# Mainboard_Motordriver_Interface.net
KiCad netlist of a schematic drawn in Altium Designer
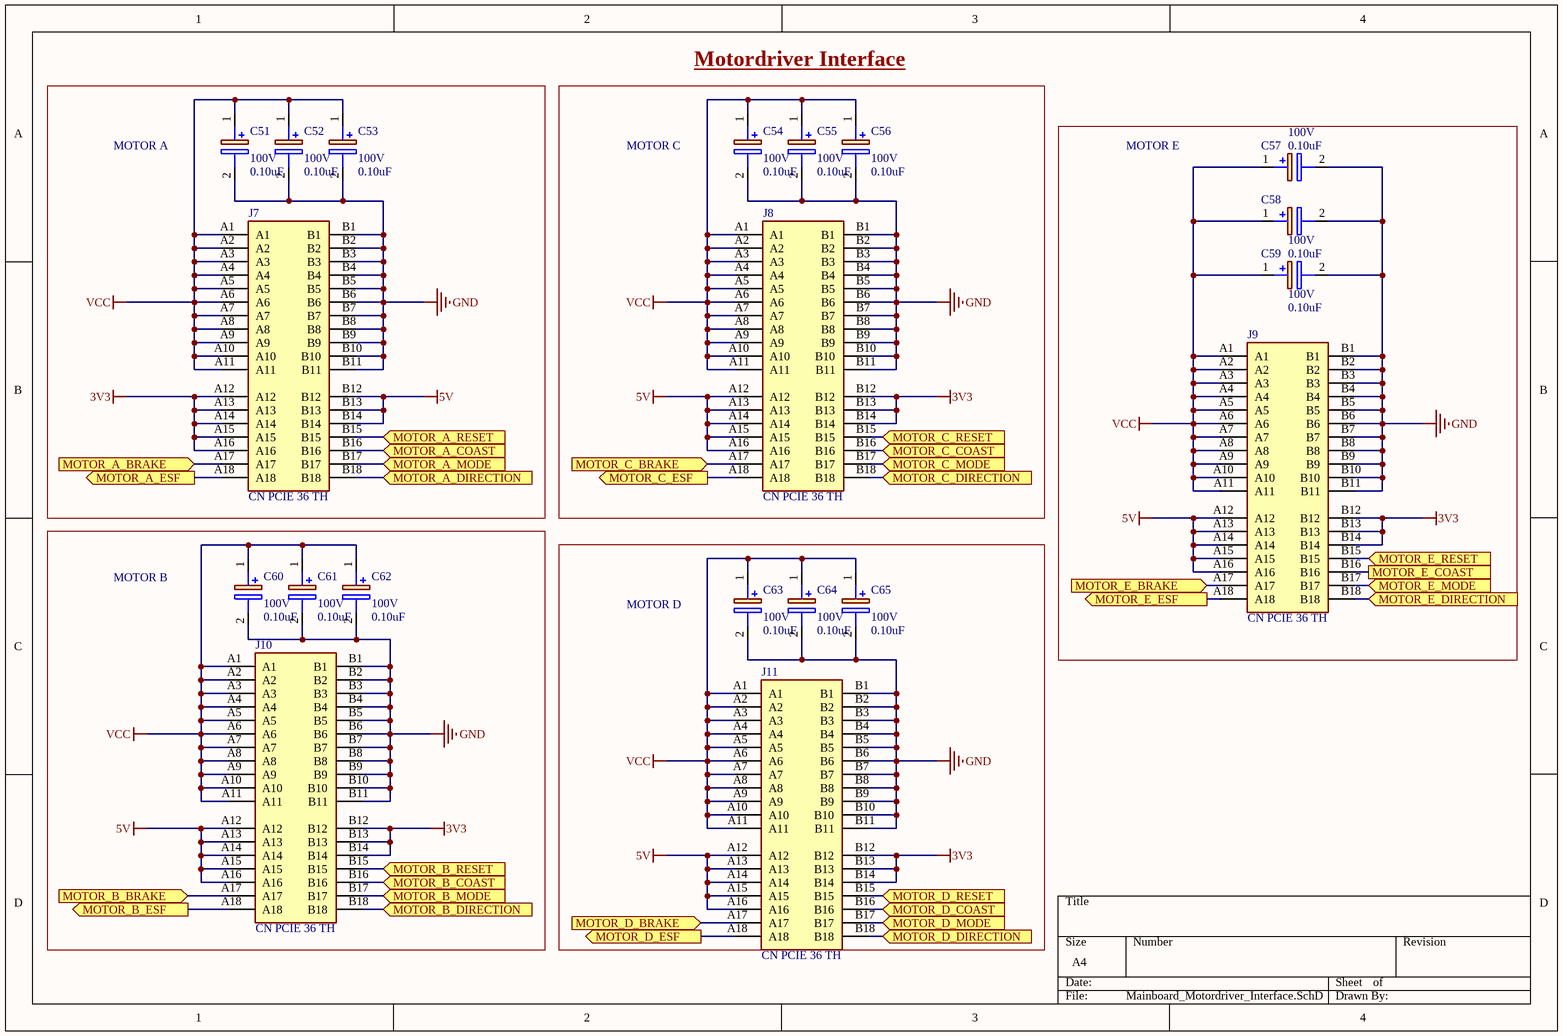
[diagram p0: Mainboard_Motordriver_Interface.SchDoc]

(export (version "E")
  (design (tool "Eeschema 10.0.6"))
  (components
    (comp (ref "C51")
      (value "0.10uF")
      (footprint "0603")
      (description "0.1µF 100V Aluminum Electrolytic Capacitors, Through-Hole, Radial, Can 2000 Hrs @ 85°C")
      (fields
        (field (name "MANUFACTURER_PART_NUMBER") "UKL2A0R1KDD")
        (field (name "MOUSER PART NUMBER") "647-UKL2A0R1KDD")
        (field (name "RATING") "100V")
      )
      (libsource (lib "") (part "CAP POL 0.1uF 100V_1"))
    )
    (comp (ref "C52")
      (value "0.10uF")
      (footprint "0603")
      (description "0.1µF 100V Aluminum Electrolytic Capacitors, Through-Hole, Radial, Can 2000 Hrs @ 85°C")
      (fields
        (field (name "MANUFACTURER_PART_NUMBER") "UKL2A0R1KDD")
        (field (name "MOUSER PART NUMBER") "647-UKL2A0R1KDD")
        (field (name "RATING") "100V")
      )
      (libsource (lib "") (part "CAP POL 0.1uF 100V_1"))
    )
    (comp (ref "C53")
      (value "0.10uF")
      (footprint "0603")
      (description "0.1µF 100V Aluminum Electrolytic Capacitors, Through-Hole, Radial, Can 2000 Hrs @ 85°C")
      (fields
        (field (name "MANUFACTURER_PART_NUMBER") "UKL2A0R1KDD")
        (field (name "MOUSER PART NUMBER") "647-UKL2A0R1KDD")
        (field (name "RATING") "100V")
      )
      (libsource (lib "") (part "CAP POL 0.1uF 100V_1"))
    )
    (comp (ref "C54")
      (value "0.10uF")
      (footprint "0603")
      (description "0.1µF 100V Aluminum Electrolytic Capacitors, Through-Hole, Radial, Can 2000 Hrs @ 85°C")
      (fields
        (field (name "MANUFACTURER_PART_NUMBER") "UKL2A0R1KDD")
        (field (name "MOUSER PART NUMBER") "647-UKL2A0R1KDD")
        (field (name "RATING") "100V")
      )
      (libsource (lib "") (part "CAP POL 0.1uF 100V_1"))
    )
    (comp (ref "C55")
      (value "0.10uF")
      (footprint "0603")
      (description "0.1µF 100V Aluminum Electrolytic Capacitors, Through-Hole, Radial, Can 2000 Hrs @ 85°C")
      (fields
        (field (name "MANUFACTURER_PART_NUMBER") "UKL2A0R1KDD")
        (field (name "MOUSER PART NUMBER") "647-UKL2A0R1KDD")
        (field (name "RATING") "100V")
      )
      (libsource (lib "") (part "CAP POL 0.1uF 100V_1"))
    )
    (comp (ref "C56")
      (value "0.10uF")
      (footprint "0603")
      (description "0.1µF 100V Aluminum Electrolytic Capacitors, Through-Hole, Radial, Can 2000 Hrs @ 85°C")
      (fields
        (field (name "MANUFACTURER_PART_NUMBER") "UKL2A0R1KDD")
        (field (name "MOUSER PART NUMBER") "647-UKL2A0R1KDD")
        (field (name "RATING") "100V")
      )
      (libsource (lib "") (part "CAP POL 0.1uF 100V_1"))
    )
    (comp (ref "C57")
      (value "0.10uF")
      (footprint "0603")
      (description "0.1µF 100V Aluminum Electrolytic Capacitors, Through-Hole, Radial, Can 2000 Hrs @ 85°C")
      (fields
        (field (name "MANUFACTURER_PART_NUMBER") "UKL2A0R1KDD")
        (field (name "MOUSER PART NUMBER") "647-UKL2A0R1KDD")
        (field (name "RATING") "100V")
      )
      (libsource (lib "AltiumLibraries") (part "CAP POL 0.1uF 100V"))
    )
    (comp (ref "C58")
      (value "0.10uF")
      (footprint "0603")
      (description "0.1µF 100V Aluminum Electrolytic Capacitors, Through-Hole, Radial, Can 2000 Hrs @ 85°C")
      (fields
        (field (name "MANUFACTURER_PART_NUMBER") "UKL2A0R1KDD")
        (field (name "MOUSER PART NUMBER") "647-UKL2A0R1KDD")
        (field (name "RATING") "100V")
      )
      (libsource (lib "AltiumLibraries") (part "CAP POL 0.1uF 100V"))
    )
    (comp (ref "C59")
      (value "0.10uF")
      (footprint "0603")
      (description "0.1µF 100V Aluminum Electrolytic Capacitors, Through-Hole, Radial, Can 2000 Hrs @ 85°C")
      (fields
        (field (name "MANUFACTURER_PART_NUMBER") "UKL2A0R1KDD")
        (field (name "MOUSER PART NUMBER") "647-UKL2A0R1KDD")
        (field (name "RATING") "100V")
      )
      (libsource (lib "AltiumLibraries") (part "CAP POL 0.1uF 100V"))
    )
    (comp (ref "C60")
      (value "0.10uF")
      (footprint "0603")
      (description "0.1µF 100V Aluminum Electrolytic Capacitors, Through-Hole, Radial, Can 2000 Hrs @ 85°C")
      (fields
        (field (name "MANUFACTURER_PART_NUMBER") "UKL2A0R1KDD")
        (field (name "MOUSER PART NUMBER") "647-UKL2A0R1KDD")
        (field (name "RATING") "100V")
      )
      (libsource (lib "") (part "CAP POL 0.1uF 100V_1"))
    )
    (comp (ref "C61")
      (value "0.10uF")
      (footprint "0603")
      (description "0.1µF 100V Aluminum Electrolytic Capacitors, Through-Hole, Radial, Can 2000 Hrs @ 85°C")
      (fields
        (field (name "MANUFACTURER_PART_NUMBER") "UKL2A0R1KDD")
        (field (name "MOUSER PART NUMBER") "647-UKL2A0R1KDD")
        (field (name "RATING") "100V")
      )
      (libsource (lib "") (part "CAP POL 0.1uF 100V_1"))
    )
    (comp (ref "C62")
      (value "0.10uF")
      (footprint "0603")
      (description "0.1µF 100V Aluminum Electrolytic Capacitors, Through-Hole, Radial, Can 2000 Hrs @ 85°C")
      (fields
        (field (name "MANUFACTURER_PART_NUMBER") "UKL2A0R1KDD")
        (field (name "MOUSER PART NUMBER") "647-UKL2A0R1KDD")
        (field (name "RATING") "100V")
      )
      (libsource (lib "") (part "CAP POL 0.1uF 100V_1"))
    )
    (comp (ref "C63")
      (value "0.10uF")
      (footprint "0603")
      (description "0.1µF 100V Aluminum Electrolytic Capacitors, Through-Hole, Radial, Can 2000 Hrs @ 85°C")
      (fields
        (field (name "MANUFACTURER_PART_NUMBER") "UKL2A0R1KDD")
        (field (name "MOUSER PART NUMBER") "647-UKL2A0R1KDD")
        (field (name "RATING") "100V")
      )
      (libsource (lib "") (part "CAP POL 0.1uF 100V_1"))
    )
    (comp (ref "C64")
      (value "0.10uF")
      (footprint "0603")
      (description "0.1µF 100V Aluminum Electrolytic Capacitors, Through-Hole, Radial, Can 2000 Hrs @ 85°C")
      (fields
        (field (name "MANUFACTURER_PART_NUMBER") "UKL2A0R1KDD")
        (field (name "MOUSER PART NUMBER") "647-UKL2A0R1KDD")
        (field (name "RATING") "100V")
      )
      (libsource (lib "") (part "CAP POL 0.1uF 100V_1"))
    )
    (comp (ref "C65")
      (value "0.10uF")
      (footprint "0603")
      (description "0.1µF 100V Aluminum Electrolytic Capacitors, Through-Hole, Radial, Can 2000 Hrs @ 85°C")
      (fields
        (field (name "MANUFACTURER_PART_NUMBER") "UKL2A0R1KDD")
        (field (name "MOUSER PART NUMBER") "647-UKL2A0R1KDD")
        (field (name "RATING") "100V")
      )
      (libsource (lib "") (part "CAP POL 0.1uF 100V_1"))
    )
    (comp (ref "J7")
      (value "CN PCIE 36 TH")
      (footprint "CN PCIE 36 TH")
      (description "36 Position Female Connector PCI Expressâ„¢ Gold 0.039 _1.00mm_ Black 10018784-10210TLF")
      (fields (field (name "MP") "10018784-10210TLF") (field (name "MF") "Amphenol ICC"))
      (libsource (lib "AltiumLibraries") (part "CN PCIE 36 TH"))
    )
    (comp (ref "J8")
      (value "CN PCIE 36 TH")
      (footprint "CN PCIE 36 TH")
      (description "36 Position Female Connector PCI Expressâ„¢ Gold 0.039 _1.00mm_ Black 10018784-10210TLF")
      (fields (field (name "MP") "10018784-10210TLF") (field (name "MF") "Amphenol ICC"))
      (libsource (lib "AltiumLibraries") (part "CN PCIE 36 TH"))
    )
    (comp (ref "J9")
      (value "CN PCIE 36 TH")
      (footprint "CN PCIE 36 TH")
      (description "36 Position Female Connector PCI Expressâ„¢ Gold 0.039 _1.00mm_ Black 10018784-10210TLF")
      (fields (field (name "MP") "10018784-10210TLF") (field (name "MF") "Amphenol ICC"))
      (libsource (lib "AltiumLibraries") (part "CN PCIE 36 TH"))
    )
    (comp (ref "J10")
      (value "CN PCIE 36 TH")
      (footprint "CN PCIE 36 TH")
      (description "36 Position Female Connector PCI Expressâ„¢ Gold 0.039 _1.00mm_ Black 10018784-10210TLF")
      (fields (field (name "MP") "10018784-10210TLF") (field (name "MF") "Amphenol ICC"))
      (libsource (lib "AltiumLibraries") (part "CN PCIE 36 TH"))
    )
    (comp (ref "J11")
      (value "CN PCIE 36 TH")
      (footprint "CN PCIE 36 TH")
      (description "36 Position Female Connector PCI Expressâ„¢ Gold 0.039 _1.00mm_ Black 10018784-10210TLF")
      (fields (field (name "MP") "10018784-10210TLF") (field (name "MF") "Amphenol ICC"))
      (libsource (lib "AltiumLibraries") (part "CN PCIE 36 TH"))
    )
  )
  (nets
    (net (code "1") (name "/MOTOR_A_BRAKE") (class "Default")
      (node (ref "J7") (pin "A17") (pinfunction "A17_A17") (pintype "passive"))
    )
    (net (code "2") (name "/MOTOR_A_COAST") (class "Default")
      (node (ref "J7") (pin "B16") (pinfunction "B16_B16") (pintype "passive"))
    )
    (net (code "3") (name "/MOTOR_A_DIRECTION") (class "Default")
      (node (ref "J7") (pin "B18") (pinfunction "B18_B18") (pintype "passive"))
    )
    (net (code "4") (name "/MOTOR_A_ESF") (class "Default")
      (node (ref "J7") (pin "A18") (pinfunction "A18_A18") (pintype "passive"))
    )
    (net (code "5") (name "/MOTOR_A_MODE") (class "Default")
      (node (ref "J7") (pin "B17") (pinfunction "B17_B17") (pintype "passive"))
    )
    (net (code "6") (name "/MOTOR_A_RESET") (class "Default")
      (node (ref "J7") (pin "B15") (pinfunction "B15_B15") (pintype "passive"))
    )
    (net (code "7") (name "/MOTOR_B_BRAKE") (class "Default")
      (node (ref "J10") (pin "A17") (pinfunction "A17_A17") (pintype "passive"))
    )
    (net (code "8") (name "/MOTOR_B_COAST") (class "Default")
      (node (ref "J10") (pin "B16") (pinfunction "B16_B16") (pintype "passive"))
    )
    (net (code "9") (name "/MOTOR_B_DIRECTION") (class "Default")
      (node (ref "J10") (pin "B18") (pinfunction "B18_B18") (pintype "passive"))
    )
    (net (code "10") (name "/MOTOR_B_ESF") (class "Default")
      (node (ref "J10") (pin "A18") (pinfunction "A18_A18") (pintype "passive"))
    )
    (net (code "11") (name "/MOTOR_B_MODE") (class "Default")
      (node (ref "J10") (pin "B17") (pinfunction "B17_B17") (pintype "passive"))
    )
    (net (code "12") (name "/MOTOR_B_RESET") (class "Default")
      (node (ref "J10") (pin "B15") (pinfunction "B15_B15") (pintype "passive"))
    )
    (net (code "13") (name "/MOTOR_C_BRAKE") (class "Default")
      (node (ref "J8") (pin "A17") (pinfunction "A17_A17") (pintype "passive"))
    )
    (net (code "14") (name "/MOTOR_C_COAST") (class "Default")
      (node (ref "J8") (pin "B16") (pinfunction "B16_B16") (pintype "passive"))
    )
    (net (code "15") (name "/MOTOR_C_DIRECTION") (class "Default")
      (node (ref "J8") (pin "B18") (pinfunction "B18_B18") (pintype "passive"))
    )
    (net (code "16") (name "/MOTOR_C_ESF") (class "Default")
      (node (ref "J8") (pin "A18") (pinfunction "A18_A18") (pintype "passive"))
    )
    (net (code "17") (name "/MOTOR_C_MODE") (class "Default")
      (node (ref "J8") (pin "B17") (pinfunction "B17_B17") (pintype "passive"))
    )
    (net (code "18") (name "/MOTOR_C_RESET") (class "Default")
      (node (ref "J8") (pin "B15") (pinfunction "B15_B15") (pintype "passive"))
    )
    (net (code "19") (name "/MOTOR_D_BRAKE") (class "Default")
      (node (ref "J11") (pin "A17") (pinfunction "A17_A17") (pintype "passive"))
    )
    (net (code "20") (name "/MOTOR_D_COAST") (class "Default")
      (node (ref "J11") (pin "B16") (pinfunction "B16_B16") (pintype "passive"))
    )
    (net (code "21") (name "/MOTOR_D_DIRECTION") (class "Default")
      (node (ref "J11") (pin "B18") (pinfunction "B18_B18") (pintype "passive"))
    )
    (net (code "22") (name "/MOTOR_D_ESF") (class "Default")
      (node (ref "J11") (pin "A18") (pinfunction "A18_A18") (pintype "passive"))
    )
    (net (code "23") (name "/MOTOR_D_MODE") (class "Default")
      (node (ref "J11") (pin "B17") (pinfunction "B17_B17") (pintype "passive"))
    )
    (net (code "24") (name "/MOTOR_D_RESET") (class "Default")
      (node (ref "J11") (pin "B15") (pinfunction "B15_B15") (pintype "passive"))
    )
    (net (code "25") (name "/MOTOR_E_BRAKE") (class "Default")
      (node (ref "J9") (pin "A17") (pinfunction "A17_A17") (pintype "passive"))
    )
    (net (code "26") (name "/MOTOR_E_COAST") (class "Default")
      (node (ref "J9") (pin "B16") (pinfunction "B16_B16") (pintype "passive"))
    )
    (net (code "27") (name "/MOTOR_E_DIRECTION") (class "Default")
      (node (ref "J9") (pin "B18") (pinfunction "B18_B18") (pintype "passive"))
    )
    (net (code "28") (name "/MOTOR_E_ESF") (class "Default")
      (node (ref "J9") (pin "A18") (pinfunction "A18_A18") (pintype "passive"))
    )
    (net (code "29") (name "/MOTOR_E_MODE") (class "Default")
      (node (ref "J9") (pin "B17") (pinfunction "B17_B17") (pintype "passive"))
    )
    (net (code "30") (name "/MOTOR_E_RESET") (class "Default")
      (node (ref "J9") (pin "B15") (pinfunction "B15_B15") (pintype "passive"))
    )
    (net (code "31") (name "3V3") (class "Default")
      (node (ref "J10") (pin "B12") (pinfunction "B12_B12") (pintype "passive"))
      (node (ref "J10") (pin "B13") (pinfunction "B13_B13") (pintype "passive"))
      (node (ref "J10") (pin "B14") (pinfunction "B14_B14") (pintype "passive"))
      (node (ref "J11") (pin "B12") (pinfunction "B12_B12") (pintype "passive"))
      (node (ref "J11") (pin "B13") (pinfunction "B13_B13") (pintype "passive"))
      (node (ref "J11") (pin "B14") (pinfunction "B14_B14") (pintype "passive"))
      (node (ref "J7") (pin "A12") (pinfunction "A12_A12") (pintype "passive"))
      (node (ref "J7") (pin "A13") (pinfunction "A13_A13") (pintype "passive"))
      (node (ref "J7") (pin "A14") (pinfunction "A14_A14") (pintype "passive"))
      (node (ref "J7") (pin "A15") (pinfunction "A15_A15") (pintype "passive"))
      (node (ref "J7") (pin "A16") (pinfunction "A16_A16") (pintype "passive"))
      (node (ref "J8") (pin "B12") (pinfunction "B12_B12") (pintype "passive"))
      (node (ref "J8") (pin "B13") (pinfunction "B13_B13") (pintype "passive"))
      (node (ref "J8") (pin "B14") (pinfunction "B14_B14") (pintype "passive"))
      (node (ref "J9") (pin "B12") (pinfunction "B12_B12") (pintype "passive"))
      (node (ref "J9") (pin "B13") (pinfunction "B13_B13") (pintype "passive"))
      (node (ref "J9") (pin "B14") (pinfunction "B14_B14") (pintype "passive"))
    )
    (net (code "32") (name "5V") (class "Default")
      (node (ref "J10") (pin "A12") (pinfunction "A12_A12") (pintype "passive"))
      (node (ref "J10") (pin "A13") (pinfunction "A13_A13") (pintype "passive"))
      (node (ref "J10") (pin "A14") (pinfunction "A14_A14") (pintype "passive"))
      (node (ref "J10") (pin "A15") (pinfunction "A15_A15") (pintype "passive"))
      (node (ref "J10") (pin "A16") (pinfunction "A16_A16") (pintype "passive"))
      (node (ref "J11") (pin "A12") (pinfunction "A12_A12") (pintype "passive"))
      (node (ref "J11") (pin "A13") (pinfunction "A13_A13") (pintype "passive"))
      (node (ref "J11") (pin "A14") (pinfunction "A14_A14") (pintype "passive"))
      (node (ref "J11") (pin "A15") (pinfunction "A15_A15") (pintype "passive"))
      (node (ref "J11") (pin "A16") (pinfunction "A16_A16") (pintype "passive"))
      (node (ref "J7") (pin "B12") (pinfunction "B12_B12") (pintype "passive"))
      (node (ref "J7") (pin "B13") (pinfunction "B13_B13") (pintype "passive"))
      (node (ref "J7") (pin "B14") (pinfunction "B14_B14") (pintype "passive"))
      (node (ref "J8") (pin "A12") (pinfunction "A12_A12") (pintype "passive"))
      (node (ref "J8") (pin "A13") (pinfunction "A13_A13") (pintype "passive"))
      (node (ref "J8") (pin "A14") (pinfunction "A14_A14") (pintype "passive"))
      (node (ref "J8") (pin "A15") (pinfunction "A15_A15") (pintype "passive"))
      (node (ref "J8") (pin "A16") (pinfunction "A16_A16") (pintype "passive"))
      (node (ref "J9") (pin "A12") (pinfunction "A12_A12") (pintype "passive"))
      (node (ref "J9") (pin "A13") (pinfunction "A13_A13") (pintype "passive"))
      (node (ref "J9") (pin "A14") (pinfunction "A14_A14") (pintype "passive"))
      (node (ref "J9") (pin "A15") (pinfunction "A15_A15") (pintype "passive"))
      (node (ref "J9") (pin "A16") (pinfunction "A16_A16") (pintype "passive"))
    )
    (net (code "33") (name "GND") (class "Default")
      (node (ref "C51") (pin "2") (pinfunction "-_2") (pintype "passive"))
      (node (ref "C52") (pin "2") (pinfunction "-_2") (pintype "passive"))
      (node (ref "C53") (pin "2") (pinfunction "-_2") (pintype "passive"))
      (node (ref "C54") (pin "2") (pinfunction "-_2") (pintype "passive"))
      (node (ref "C55") (pin "2") (pinfunction "-_2") (pintype "passive"))
      (node (ref "C56") (pin "2") (pinfunction "-_2") (pintype "passive"))
      (node (ref "C57") (pin "2") (pinfunction "-_2") (pintype "passive"))
      (node (ref "C58") (pin "2") (pinfunction "-_2") (pintype "passive"))
      (node (ref "C59") (pin "2") (pinfunction "-_2") (pintype "passive"))
      (node (ref "C60") (pin "2") (pinfunction "-_2") (pintype "passive"))
      (node (ref "C61") (pin "2") (pinfunction "-_2") (pintype "passive"))
      (node (ref "C62") (pin "2") (pinfunction "-_2") (pintype "passive"))
      (node (ref "C63") (pin "2") (pinfunction "-_2") (pintype "passive"))
      (node (ref "C64") (pin "2") (pinfunction "-_2") (pintype "passive"))
      (node (ref "C65") (pin "2") (pinfunction "-_2") (pintype "passive"))
      (node (ref "J10") (pin "B1") (pinfunction "B1_B1") (pintype "passive"))
      (node (ref "J10") (pin "B10") (pinfunction "B10_B10") (pintype "passive"))
      (node (ref "J10") (pin "B11") (pinfunction "B11_B11") (pintype "passive"))
      (node (ref "J10") (pin "B2") (pinfunction "B2_B2") (pintype "passive"))
      (node (ref "J10") (pin "B3") (pinfunction "B3_B3") (pintype "passive"))
      (node (ref "J10") (pin "B4") (pinfunction "B4_B4") (pintype "passive"))
      (node (ref "J10") (pin "B5") (pinfunction "B5_B5") (pintype "passive"))
      (node (ref "J10") (pin "B6") (pinfunction "B6_B6") (pintype "passive"))
      (node (ref "J10") (pin "B7") (pinfunction "B7_B7") (pintype "passive"))
      (node (ref "J10") (pin "B8") (pinfunction "B8_B8") (pintype "passive"))
      (node (ref "J10") (pin "B9") (pinfunction "B9_B9") (pintype "passive"))
      (node (ref "J11") (pin "B1") (pinfunction "B1_B1") (pintype "passive"))
      (node (ref "J11") (pin "B10") (pinfunction "B10_B10") (pintype "passive"))
      (node (ref "J11") (pin "B11") (pinfunction "B11_B11") (pintype "passive"))
      (node (ref "J11") (pin "B2") (pinfunction "B2_B2") (pintype "passive"))
      (node (ref "J11") (pin "B3") (pinfunction "B3_B3") (pintype "passive"))
      (node (ref "J11") (pin "B4") (pinfunction "B4_B4") (pintype "passive"))
      (node (ref "J11") (pin "B5") (pinfunction "B5_B5") (pintype "passive"))
      (node (ref "J11") (pin "B6") (pinfunction "B6_B6") (pintype "passive"))
      (node (ref "J11") (pin "B7") (pinfunction "B7_B7") (pintype "passive"))
      (node (ref "J11") (pin "B8") (pinfunction "B8_B8") (pintype "passive"))
      (node (ref "J11") (pin "B9") (pinfunction "B9_B9") (pintype "passive"))
      (node (ref "J7") (pin "B1") (pinfunction "B1_B1") (pintype "passive"))
      (node (ref "J7") (pin "B10") (pinfunction "B10_B10") (pintype "passive"))
      (node (ref "J7") (pin "B11") (pinfunction "B11_B11") (pintype "passive"))
      (node (ref "J7") (pin "B2") (pinfunction "B2_B2") (pintype "passive"))
      (node (ref "J7") (pin "B3") (pinfunction "B3_B3") (pintype "passive"))
      (node (ref "J7") (pin "B4") (pinfunction "B4_B4") (pintype "passive"))
      (node (ref "J7") (pin "B5") (pinfunction "B5_B5") (pintype "passive"))
      (node (ref "J7") (pin "B6") (pinfunction "B6_B6") (pintype "passive"))
      (node (ref "J7") (pin "B7") (pinfunction "B7_B7") (pintype "passive"))
      (node (ref "J7") (pin "B8") (pinfunction "B8_B8") (pintype "passive"))
      (node (ref "J7") (pin "B9") (pinfunction "B9_B9") (pintype "passive"))
      (node (ref "J8") (pin "B1") (pinfunction "B1_B1") (pintype "passive"))
      (node (ref "J8") (pin "B10") (pinfunction "B10_B10") (pintype "passive"))
      (node (ref "J8") (pin "B11") (pinfunction "B11_B11") (pintype "passive"))
      (node (ref "J8") (pin "B2") (pinfunction "B2_B2") (pintype "passive"))
      (node (ref "J8") (pin "B3") (pinfunction "B3_B3") (pintype "passive"))
      (node (ref "J8") (pin "B4") (pinfunction "B4_B4") (pintype "passive"))
      (node (ref "J8") (pin "B5") (pinfunction "B5_B5") (pintype "passive"))
      (node (ref "J8") (pin "B6") (pinfunction "B6_B6") (pintype "passive"))
      (node (ref "J8") (pin "B7") (pinfunction "B7_B7") (pintype "passive"))
      (node (ref "J8") (pin "B8") (pinfunction "B8_B8") (pintype "passive"))
      (node (ref "J8") (pin "B9") (pinfunction "B9_B9") (pintype "passive"))
      (node (ref "J9") (pin "B1") (pinfunction "B1_B1") (pintype "passive"))
      (node (ref "J9") (pin "B10") (pinfunction "B10_B10") (pintype "passive"))
      (node (ref "J9") (pin "B11") (pinfunction "B11_B11") (pintype "passive"))
      (node (ref "J9") (pin "B2") (pinfunction "B2_B2") (pintype "passive"))
      (node (ref "J9") (pin "B3") (pinfunction "B3_B3") (pintype "passive"))
      (node (ref "J9") (pin "B4") (pinfunction "B4_B4") (pintype "passive"))
      (node (ref "J9") (pin "B5") (pinfunction "B5_B5") (pintype "passive"))
      (node (ref "J9") (pin "B6") (pinfunction "B6_B6") (pintype "passive"))
      (node (ref "J9") (pin "B7") (pinfunction "B7_B7") (pintype "passive"))
      (node (ref "J9") (pin "B8") (pinfunction "B8_B8") (pintype "passive"))
      (node (ref "J9") (pin "B9") (pinfunction "B9_B9") (pintype "passive"))
    )
    (net (code "34") (name "VCC") (class "Default")
      (node (ref "C51") (pin "1") (pinfunction "+_1") (pintype "passive"))
      (node (ref "C52") (pin "1") (pinfunction "+_1") (pintype "passive"))
      (node (ref "C53") (pin "1") (pinfunction "+_1") (pintype "passive"))
      (node (ref "C54") (pin "1") (pinfunction "+_1") (pintype "passive"))
      (node (ref "C55") (pin "1") (pinfunction "+_1") (pintype "passive"))
      (node (ref "C56") (pin "1") (pinfunction "+_1") (pintype "passive"))
      (node (ref "C57") (pin "1") (pinfunction "+_1") (pintype "passive"))
      (node (ref "C58") (pin "1") (pinfunction "+_1") (pintype "passive"))
      (node (ref "C59") (pin "1") (pinfunction "+_1") (pintype "passive"))
      (node (ref "C60") (pin "1") (pinfunction "+_1") (pintype "passive"))
      (node (ref "C61") (pin "1") (pinfunction "+_1") (pintype "passive"))
      (node (ref "C62") (pin "1") (pinfunction "+_1") (pintype "passive"))
      (node (ref "C63") (pin "1") (pinfunction "+_1") (pintype "passive"))
      (node (ref "C64") (pin "1") (pinfunction "+_1") (pintype "passive"))
      (node (ref "C65") (pin "1") (pinfunction "+_1") (pintype "passive"))
      (node (ref "J10") (pin "A1") (pinfunction "A1_A1") (pintype "passive"))
      (node (ref "J10") (pin "A10") (pinfunction "A10_A10") (pintype "passive"))
      (node (ref "J10") (pin "A11") (pinfunction "A11_A11") (pintype "passive"))
      (node (ref "J10") (pin "A2") (pinfunction "A2_A2") (pintype "passive"))
      (node (ref "J10") (pin "A3") (pinfunction "A3_A3") (pintype "passive"))
      (node (ref "J10") (pin "A4") (pinfunction "A4_A4") (pintype "passive"))
      (node (ref "J10") (pin "A5") (pinfunction "A5_A5") (pintype "passive"))
      (node (ref "J10") (pin "A6") (pinfunction "A6_A6") (pintype "passive"))
      (node (ref "J10") (pin "A7") (pinfunction "A7_A7") (pintype "passive"))
      (node (ref "J10") (pin "A8") (pinfunction "A8_A8") (pintype "passive"))
      (node (ref "J10") (pin "A9") (pinfunction "A9_A9") (pintype "passive"))
      (node (ref "J11") (pin "A1") (pinfunction "A1_A1") (pintype "passive"))
      (node (ref "J11") (pin "A10") (pinfunction "A10_A10") (pintype "passive"))
      (node (ref "J11") (pin "A11") (pinfunction "A11_A11") (pintype "passive"))
      (node (ref "J11") (pin "A2") (pinfunction "A2_A2") (pintype "passive"))
      (node (ref "J11") (pin "A3") (pinfunction "A3_A3") (pintype "passive"))
      (node (ref "J11") (pin "A4") (pinfunction "A4_A4") (pintype "passive"))
      (node (ref "J11") (pin "A5") (pinfunction "A5_A5") (pintype "passive"))
      (node (ref "J11") (pin "A6") (pinfunction "A6_A6") (pintype "passive"))
      (node (ref "J11") (pin "A7") (pinfunction "A7_A7") (pintype "passive"))
      (node (ref "J11") (pin "A8") (pinfunction "A8_A8") (pintype "passive"))
      (node (ref "J11") (pin "A9") (pinfunction "A9_A9") (pintype "passive"))
      (node (ref "J7") (pin "A1") (pinfunction "A1_A1") (pintype "passive"))
      (node (ref "J7") (pin "A10") (pinfunction "A10_A10") (pintype "passive"))
      (node (ref "J7") (pin "A11") (pinfunction "A11_A11") (pintype "passive"))
      (node (ref "J7") (pin "A2") (pinfunction "A2_A2") (pintype "passive"))
      (node (ref "J7") (pin "A3") (pinfunction "A3_A3") (pintype "passive"))
      (node (ref "J7") (pin "A4") (pinfunction "A4_A4") (pintype "passive"))
      (node (ref "J7") (pin "A5") (pinfunction "A5_A5") (pintype "passive"))
      (node (ref "J7") (pin "A6") (pinfunction "A6_A6") (pintype "passive"))
      (node (ref "J7") (pin "A7") (pinfunction "A7_A7") (pintype "passive"))
      (node (ref "J7") (pin "A8") (pinfunction "A8_A8") (pintype "passive"))
      (node (ref "J7") (pin "A9") (pinfunction "A9_A9") (pintype "passive"))
      (node (ref "J8") (pin "A1") (pinfunction "A1_A1") (pintype "passive"))
      (node (ref "J8") (pin "A10") (pinfunction "A10_A10") (pintype "passive"))
      (node (ref "J8") (pin "A11") (pinfunction "A11_A11") (pintype "passive"))
      (node (ref "J8") (pin "A2") (pinfunction "A2_A2") (pintype "passive"))
      (node (ref "J8") (pin "A3") (pinfunction "A3_A3") (pintype "passive"))
      (node (ref "J8") (pin "A4") (pinfunction "A4_A4") (pintype "passive"))
      (node (ref "J8") (pin "A5") (pinfunction "A5_A5") (pintype "passive"))
      (node (ref "J8") (pin "A6") (pinfunction "A6_A6") (pintype "passive"))
      (node (ref "J8") (pin "A7") (pinfunction "A7_A7") (pintype "passive"))
      (node (ref "J8") (pin "A8") (pinfunction "A8_A8") (pintype "passive"))
      (node (ref "J8") (pin "A9") (pinfunction "A9_A9") (pintype "passive"))
      (node (ref "J9") (pin "A1") (pinfunction "A1_A1") (pintype "passive"))
      (node (ref "J9") (pin "A10") (pinfunction "A10_A10") (pintype "passive"))
      (node (ref "J9") (pin "A11") (pinfunction "A11_A11") (pintype "passive"))
      (node (ref "J9") (pin "A2") (pinfunction "A2_A2") (pintype "passive"))
      (node (ref "J9") (pin "A3") (pinfunction "A3_A3") (pintype "passive"))
      (node (ref "J9") (pin "A4") (pinfunction "A4_A4") (pintype "passive"))
      (node (ref "J9") (pin "A5") (pinfunction "A5_A5") (pintype "passive"))
      (node (ref "J9") (pin "A6") (pinfunction "A6_A6") (pintype "passive"))
      (node (ref "J9") (pin "A7") (pinfunction "A7_A7") (pintype "passive"))
      (node (ref "J9") (pin "A8") (pinfunction "A8_A8") (pintype "passive"))
      (node (ref "J9") (pin "A9") (pinfunction "A9_A9") (pintype "passive"))
    )
  )
)
